# Ignitors_SCH.net
KiCad netlist of a schematic drawn in Altium Designer
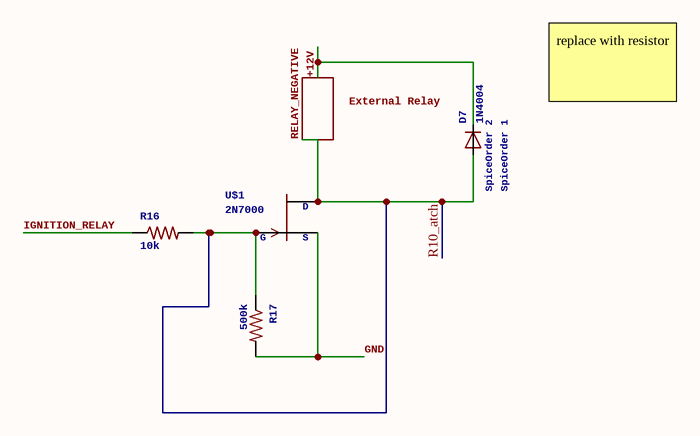
[diagram p0: Ignitors_SCH.SchDoc]

(export (version "E")
  (design (tool "Eeschema 10.0.6"))
  (components
    (comp (ref "D7")
      (value "1N4004")
      (footprint "DO41-10")
      (description "DIODEgeneral purpose rectifier, 1 A")
      (fields (field (name "SPICEORDER1") "SpiceOrder 1") (field (name "SPICEORDER2") "SpiceOrder 2"))
      (libsource (lib "diode") (part "1N4004"))
    )
    (comp (ref "R16")
      (value "10k")
      (footprint "R0805")
      (description "RESISTOR, American symbol")
      (libsource (lib "rcl") (part "R-US_R0805"))
    )
    (comp (ref "R17")
      (value "500k")
      (footprint "R0805")
      (description "RESISTOR, American symbol")
      (libsource (lib "rcl") (part "R-US_R0805"))
    )
    (comp (ref "U$1")
      (value "2N7000")
      (footprint "SOT23")
      (fields
        (field (name "D") "D")
        (field (name "S") "S")
        (field (name "G") "G")
        (field (name "LIBRARYNAME") "transistor-fet-extra")
      )
      (libsource (lib "transistor-fet-extra") (part "2N7000"))
    )
  )
  (nets
    (net (code "1") (name "/+12V") (class "Default")
      (node (ref "D7") (pin "C") (pinfunction "C_C") (pintype "passive"))
    )
    (net (code "2") (name "/GND") (class "Default")
      (node (ref "R17") (pin "2") (pinfunction "2_2") (pintype "passive"))
      (node (ref "U$1") (pin "2") (pinfunction "S_2") (pintype "passive"))
    )
    (net (code "3") (name "/IGNITION_RELAY") (class "Default")
      (node (ref "R16") (pin "1") (pinfunction "1_1") (pintype "passive"))
    )
    (net (code "4") (name "/R10_atch") (class "Default")
      (node (ref "D7") (pin "A") (pinfunction "A_A") (pintype "passive"))
      (node (ref "R16") (pin "2") (pinfunction "2_2") (pintype "passive"))
      (node (ref "R17") (pin "1") (pinfunction "1_1") (pintype "passive"))
      (node (ref "U$1") (pin "1") (pinfunction "G_1") (pintype "passive"))
      (node (ref "U$1") (pin "3") (pinfunction "D_3") (pintype "passive"))
    )
  )
)
